# vestee_main.net
KiCad netlist of a schematic drawn in EAGLE
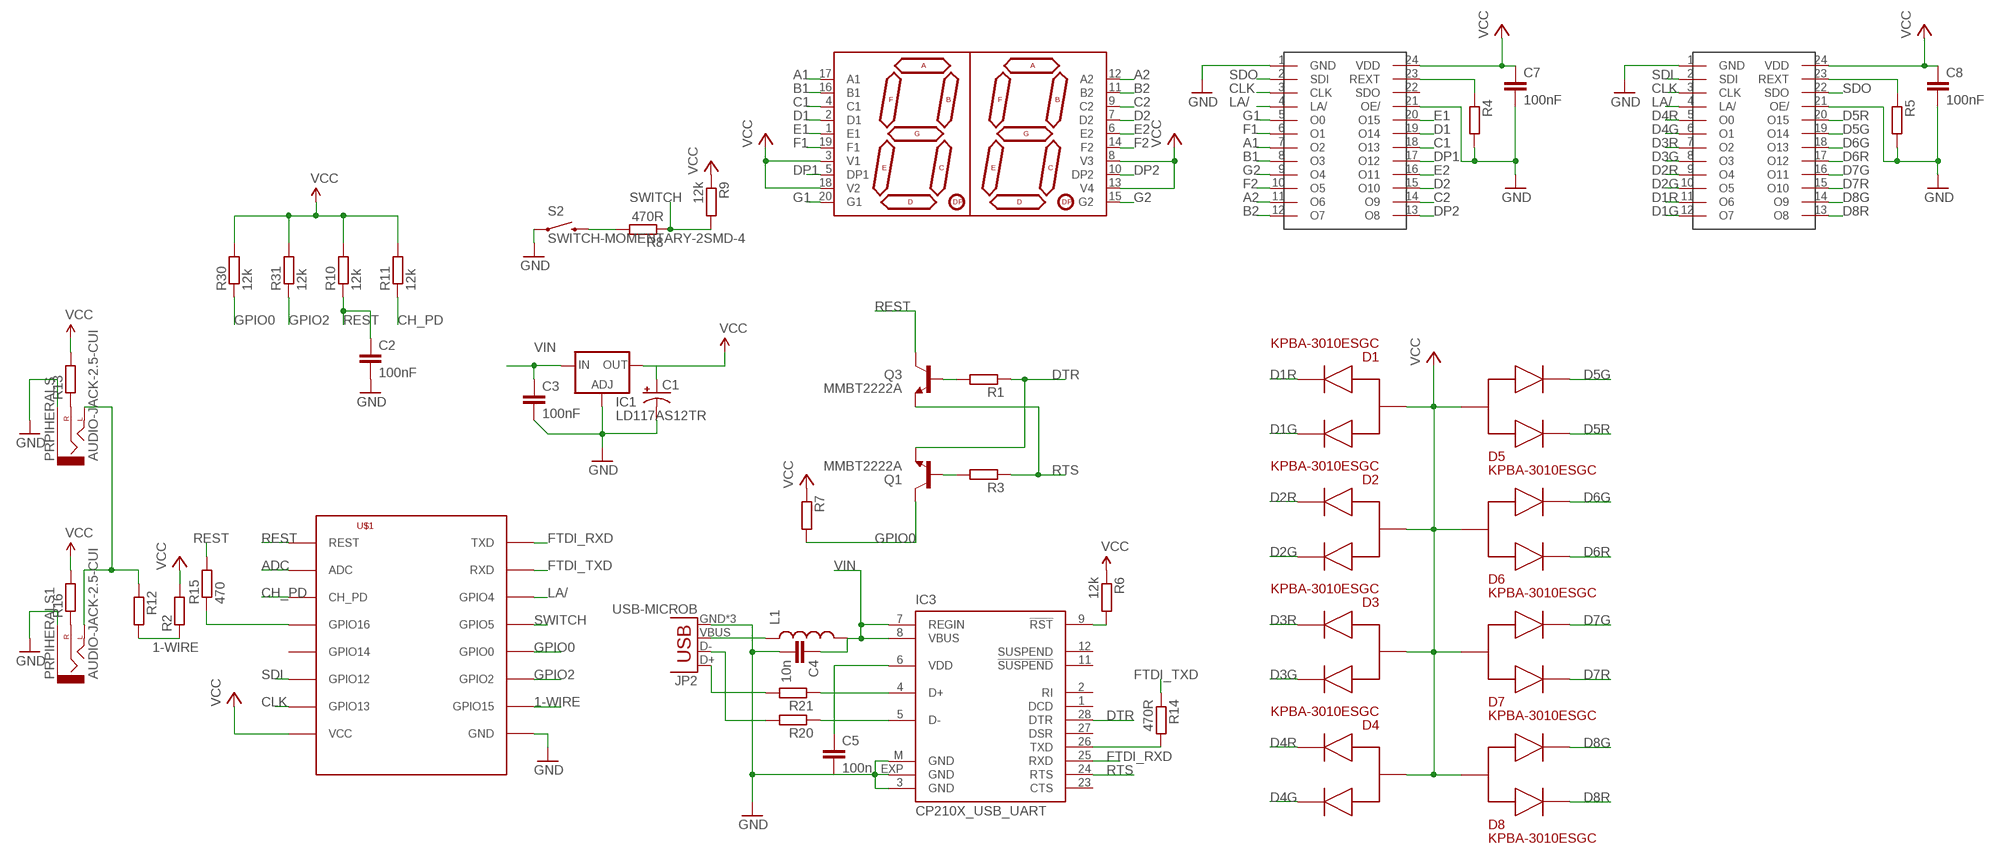
[diagram p0: schematic, sheet 1]

(export (version "E")
  (design (tool "Eeschema 10.0.6"))
  (components
    (comp (ref "C1")
      (value "CAP_POL3528")
      (footprint "eagle-import:EIA3528")
      (libsource (lib "eagle-import") (part "CAP_POL3528"))
    )
    (comp (ref "C2")
      (value "100nF")
      (footprint "eagle-import:C0603")
      (libsource (lib "eagle-import") (part "C-EUC0603"))
    )
    (comp (ref "C3")
      (value "100nF")
      (footprint "eagle-import:C0603")
      (libsource (lib "eagle-import") (part "C-EUC0603"))
    )
    (comp (ref "C4")
      (value "10n")
      (footprint "eagle-import:C0603")
      (libsource (lib "eagle-import") (part "C-EUC0603"))
    )
    (comp (ref "C5")
      (value "100n")
      (footprint "eagle-import:C0603")
      (libsource (lib "eagle-import") (part "C-EUC0603"))
    )
    (comp (ref "C7")
      (value "100nF")
      (footprint "eagle-import:C0603")
      (libsource (lib "eagle-import") (part "C-EUC0603"))
    )
    (comp (ref "C8")
      (value "100nF")
      (footprint "eagle-import:C0603")
      (libsource (lib "eagle-import") (part "C-EUC0603"))
    )
    (comp (ref "D1")
      (value "KPBA-3010ESGC")
      (footprint "eagle-import:APA3010SF4C")
      (libsource (lib "eagle-import") (part "APA3010SF4C"))
    )
    (comp (ref "D2")
      (value "KPBA-3010ESGC")
      (footprint "eagle-import:APA3010SF4C")
      (libsource (lib "eagle-import") (part "APA3010SF4C"))
    )
    (comp (ref "D3")
      (value "KPBA-3010ESGC")
      (footprint "eagle-import:APA3010SF4C")
      (libsource (lib "eagle-import") (part "APA3010SF4C"))
    )
    (comp (ref "D4")
      (value "KPBA-3010ESGC")
      (footprint "eagle-import:APA3010SF4C")
      (libsource (lib "eagle-import") (part "APA3010SF4C"))
    )
    (comp (ref "D5")
      (value "KPBA-3010ESGC")
      (footprint "eagle-import:APA3010SF4C")
      (libsource (lib "eagle-import") (part "APA3010SF4C"))
    )
    (comp (ref "D6")
      (value "KPBA-3010ESGC")
      (footprint "eagle-import:APA3010SF4C")
      (libsource (lib "eagle-import") (part "APA3010SF4C"))
    )
    (comp (ref "D7")
      (value "KPBA-3010ESGC")
      (footprint "eagle-import:APA3010SF4C")
      (libsource (lib "eagle-import") (part "APA3010SF4C"))
    )
    (comp (ref "D8")
      (value "KPBA-3010ESGC")
      (footprint "eagle-import:APA3010SF4C")
      (libsource (lib "eagle-import") (part "APA3010SF4C"))
    )
    (comp (ref "IC1")
      (value "LD117AS12TR")
      (footprint "eagle-import:SOT223")
      (libsource (lib "eagle-import") (part "LD117A?S12TR"))
    )
    (comp (ref "IC3")
      (value "CP210X_USB_UART")
      (footprint "eagle-import:MLP28")
      (libsource (lib "eagle-import") (part "CP210X_USB_UART"))
    )
    (comp (ref "JP2")
      (value "USB-MICROB")
      (footprint "eagle-import:USB-MICROB")
      (libsource (lib "eagle-import") (part "USB-MICROB"))
    )
    (comp (ref "L1")
      (value "INDUCTOR1210")
      (footprint "eagle-import:1210")
      (libsource (lib "eagle-import") (part "INDUCTOR1210"))
    )
    (comp (ref "PRPIHERALS")
      (value "AUDIO-JACK-2.5-CUI")
      (footprint "eagle-import:STEREOJACK2.5_SMD_CUI")
      (libsource (lib "eagle-import") (part "AUDIO-JACK-2.5-CUI"))
    )
    (comp (ref "PRPIHERALS1")
      (value "AUDIO-JACK-2.5-CUI")
      (footprint "eagle-import:STEREOJACK2.5_SMD_CUI")
      (libsource (lib "eagle-import") (part "AUDIO-JACK-2.5-CUI"))
    )
    (comp (ref "Q1")
      (value "MMBT2222A")
      (footprint "eagle-import:SOT23-3")
      (libsource (lib "eagle-import") (part "TRANSISTOR_NPNMMBT2222A"))
    )
    (comp (ref "Q3")
      (value "MMBT2222A")
      (footprint "eagle-import:SOT23-3")
      (libsource (lib "eagle-import") (part "TRANSISTOR_NPNMMBT2222A"))
    )
    (comp (ref "R1")
      (value "R-EU_R0603")
      (footprint "eagle-import:R0603")
      (libsource (lib "eagle-import") (part "R-EU_R0603"))
    )
    (comp (ref "R2")
      (value "R-EU_R0603")
      (footprint "eagle-import:R0603")
      (libsource (lib "eagle-import") (part "R-EU_R0603"))
    )
    (comp (ref "R3")
      (value "R-EU_R0603")
      (footprint "eagle-import:R0603")
      (libsource (lib "eagle-import") (part "R-EU_R0603"))
    )
    (comp (ref "R4")
      (value "R-EU_R0603")
      (footprint "eagle-import:R0603")
      (libsource (lib "eagle-import") (part "R-EU_R0603"))
    )
    (comp (ref "R5")
      (value "R-EU_R0603")
      (footprint "eagle-import:R0603")
      (libsource (lib "eagle-import") (part "R-EU_R0603"))
    )
    (comp (ref "R6")
      (value "12k")
      (footprint "eagle-import:R0603")
      (libsource (lib "eagle-import") (part "R-EU_R0603"))
    )
    (comp (ref "R7")
      (value "R-EU_R0603")
      (footprint "eagle-import:R0603")
      (libsource (lib "eagle-import") (part "R-EU_R0603"))
    )
    (comp (ref "R8")
      (value "470R")
      (footprint "eagle-import:R0603")
      (libsource (lib "eagle-import") (part "R-EU_R0603"))
    )
    (comp (ref "R9")
      (value "12k")
      (footprint "eagle-import:R0603")
      (libsource (lib "eagle-import") (part "R-EU_R0603"))
    )
    (comp (ref "R10")
      (value "12k")
      (footprint "eagle-import:R0603")
      (libsource (lib "eagle-import") (part "R-EU_R0603"))
    )
    (comp (ref "R11")
      (value "12k")
      (footprint "eagle-import:R0603")
      (libsource (lib "eagle-import") (part "R-EU_R0603"))
    )
    (comp (ref "R12")
      (value "R-EU_R0603")
      (footprint "eagle-import:R0603")
      (libsource (lib "eagle-import") (part "R-EU_R0603"))
    )
    (comp (ref "R13")
      (value "R-EU_M1206")
      (footprint "eagle-import:M1206")
      (libsource (lib "eagle-import") (part "R-EU_M1206"))
    )
    (comp (ref "R14")
      (value "470R")
      (footprint "eagle-import:R0603")
      (libsource (lib "eagle-import") (part "R-EU_R0603"))
    )
    (comp (ref "R15")
      (value "470")
      (footprint "eagle-import:R0603")
      (libsource (lib "eagle-import") (part "R-EU_R0603"))
    )
    (comp (ref "R16")
      (value "R-EU_M1206")
      (footprint "eagle-import:M1206")
      (libsource (lib "eagle-import") (part "R-EU_M1206"))
    )
    (comp (ref "R20")
      (value "R-EU_R0603")
      (footprint "eagle-import:R0603")
      (libsource (lib "eagle-import") (part "R-EU_R0603"))
    )
    (comp (ref "R21")
      (value "R-EU_R0603")
      (footprint "eagle-import:R0603")
      (libsource (lib "eagle-import") (part "R-EU_R0603"))
    )
    (comp (ref "R30")
      (value "12k")
      (footprint "eagle-import:R0603")
      (libsource (lib "eagle-import") (part "R-EU_R0603"))
    )
    (comp (ref "R31")
      (value "12k")
      (footprint "eagle-import:R0603")
      (libsource (lib "eagle-import") (part "R-EU_R0603"))
    )
    (comp (ref "S2")
      (value "SWITCH-MOMENTARY-2SMD-4")
      (footprint "eagle-import:TACTILE_SWITCH_TALL")
      (libsource (lib "eagle-import") (part "SWITCH-MOMENTARY-2SMD-4"))
    )
    (comp (ref "U$1")
      (value "ESP8266-07")
      (footprint "eagle-import:ESP-07")
      (libsource (lib "eagle-import") (part "ESP8266-07"))
    )
    (comp (ref "U$2")
      (value "KCDA02-103")
      (footprint "eagle-import:KCDA02-103")
      (libsource (lib "eagle-import") (part "KCDA02-103"))
    )
    (comp (ref "U$3")
      (value "SCT2024CSSG")
      (footprint "eagle-import:SSOP24")
      (libsource (lib "eagle-import") (part "SCT2024CSSG"))
    )
    (comp (ref "U$4")
      (value "SCT2024CSSG")
      (footprint "eagle-import:SSOP24")
      (libsource (lib "eagle-import") (part "SCT2024CSSG"))
    )
  )
  (nets
    (net (code "1") (name "/1-WIRE") (class "Default")
      (node (ref "R12") (pin "2") (pinfunction "2_2") (pintype "passive"))
      (node (ref "R2") (pin "1") (pinfunction "1_1") (pintype "passive"))
      (node (ref "U$1") (pin "GPIO15") (pinfunction "GPIO15_GPIO15") (pintype "input"))
    )
    (net (code "2") (name "/A1") (class "Default")
      (node (ref "U$2") (pin "17") (pinfunction "A1_17") (pintype "bidirectional"))
      (node (ref "U$3") (pin "7") (pinfunction "O2_7") (pintype "bidirectional"))
    )
    (net (code "3") (name "/A2") (class "Default")
      (node (ref "U$2") (pin "12") (pinfunction "A2_12") (pintype "bidirectional"))
      (node (ref "U$3") (pin "11") (pinfunction "O6_11") (pintype "bidirectional"))
    )
    (net (code "4") (name "/ADC") (class "Default")
      (node (ref "U$1") (pin "ADC") (pinfunction "ADC_ADC") (pintype "bidirectional"))
    )
    (net (code "5") (name "/B1") (class "Default")
      (node (ref "U$2") (pin "16") (pinfunction "B1_16") (pintype "bidirectional"))
      (node (ref "U$3") (pin "8") (pinfunction "O3_8") (pintype "bidirectional"))
    )
    (net (code "6") (name "/B2") (class "Default")
      (node (ref "U$2") (pin "11") (pinfunction "B2_11") (pintype "bidirectional"))
      (node (ref "U$3") (pin "12") (pinfunction "O7_12") (pintype "bidirectional"))
    )
    (net (code "7") (name "/C1") (class "Default")
      (node (ref "U$2") (pin "4") (pinfunction "C1_4") (pintype "bidirectional"))
      (node (ref "U$3") (pin "18") (pinfunction "O13_18") (pintype "bidirectional"))
    )
    (net (code "8") (name "/C2") (class "Default")
      (node (ref "U$2") (pin "9") (pinfunction "C2_9") (pintype "bidirectional"))
      (node (ref "U$3") (pin "14") (pinfunction "O9_14") (pintype "bidirectional"))
    )
    (net (code "9") (name "/CH_PD") (class "Default")
      (node (ref "R11") (pin "1") (pinfunction "1_1") (pintype "passive"))
      (node (ref "U$1") (pin "CH_PD") (pinfunction "CH_PD_CH_PD") (pintype "input"))
    )
    (net (code "10") (name "/CLK") (class "Default")
      (node (ref "U$1") (pin "GPIO13") (pinfunction "GPIO13_GPIO13") (pintype "bidirectional"))
      (node (ref "U$3") (pin "3") (pinfunction "CLK_3") (pintype "bidirectional"))
      (node (ref "U$4") (pin "3") (pinfunction "CLK_3") (pintype "bidirectional"))
    )
    (net (code "11") (name "/D1") (class "Default")
      (node (ref "U$2") (pin "2") (pinfunction "D1_2") (pintype "bidirectional"))
      (node (ref "U$3") (pin "19") (pinfunction "O14_19") (pintype "bidirectional"))
    )
    (net (code "12") (name "/D1G") (class "Default")
      (node (ref "D1") (pin "3") (pinfunction "3_3") (pintype "bidirectional"))
      (node (ref "U$4") (pin "12") (pinfunction "O7_12") (pintype "bidirectional"))
    )
    (net (code "13") (name "/D1R") (class "Default")
      (node (ref "D1") (pin "2") (pinfunction "2_2") (pintype "bidirectional"))
      (node (ref "U$4") (pin "11") (pinfunction "O6_11") (pintype "bidirectional"))
    )
    (net (code "14") (name "/D2") (class "Default")
      (node (ref "U$2") (pin "7") (pinfunction "D2_7") (pintype "bidirectional"))
      (node (ref "U$3") (pin "15") (pinfunction "O10_15") (pintype "bidirectional"))
    )
    (net (code "15") (name "/D2G") (class "Default")
      (node (ref "D2") (pin "3") (pinfunction "3_3") (pintype "bidirectional"))
      (node (ref "U$4") (pin "10") (pinfunction "O5_10") (pintype "bidirectional"))
    )
    (net (code "16") (name "/D2R") (class "Default")
      (node (ref "D2") (pin "2") (pinfunction "2_2") (pintype "bidirectional"))
      (node (ref "U$4") (pin "9") (pinfunction "O4_9") (pintype "bidirectional"))
    )
    (net (code "17") (name "/D3G") (class "Default")
      (node (ref "D3") (pin "3") (pinfunction "3_3") (pintype "bidirectional"))
      (node (ref "U$4") (pin "8") (pinfunction "O3_8") (pintype "bidirectional"))
    )
    (net (code "18") (name "/D3R") (class "Default")
      (node (ref "D3") (pin "2") (pinfunction "2_2") (pintype "bidirectional"))
      (node (ref "U$4") (pin "7") (pinfunction "O2_7") (pintype "bidirectional"))
    )
    (net (code "19") (name "/D4G") (class "Default")
      (node (ref "D4") (pin "3") (pinfunction "3_3") (pintype "bidirectional"))
      (node (ref "U$4") (pin "6") (pinfunction "O1_6") (pintype "bidirectional"))
    )
    (net (code "20") (name "/D4R") (class "Default")
      (node (ref "D4") (pin "2") (pinfunction "2_2") (pintype "bidirectional"))
      (node (ref "U$4") (pin "5") (pinfunction "O0_5") (pintype "bidirectional"))
    )
    (net (code "21") (name "/D5G") (class "Default")
      (node (ref "D5") (pin "3") (pinfunction "3_3") (pintype "bidirectional"))
      (node (ref "U$4") (pin "19") (pinfunction "O14_19") (pintype "bidirectional"))
    )
    (net (code "22") (name "/D5R") (class "Default")
      (node (ref "D5") (pin "2") (pinfunction "2_2") (pintype "bidirectional"))
      (node (ref "U$4") (pin "20") (pinfunction "O15_20") (pintype "bidirectional"))
    )
    (net (code "23") (name "/D6G") (class "Default")
      (node (ref "D6") (pin "3") (pinfunction "3_3") (pintype "bidirectional"))
      (node (ref "U$4") (pin "18") (pinfunction "O13_18") (pintype "bidirectional"))
    )
    (net (code "24") (name "/D6R") (class "Default")
      (node (ref "D6") (pin "2") (pinfunction "2_2") (pintype "bidirectional"))
      (node (ref "U$4") (pin "17") (pinfunction "O12_17") (pintype "bidirectional"))
    )
    (net (code "25") (name "/D7G") (class "Default")
      (node (ref "D7") (pin "3") (pinfunction "3_3") (pintype "bidirectional"))
      (node (ref "U$4") (pin "16") (pinfunction "O11_16") (pintype "bidirectional"))
    )
    (net (code "26") (name "/D7R") (class "Default")
      (node (ref "D7") (pin "2") (pinfunction "2_2") (pintype "bidirectional"))
      (node (ref "U$4") (pin "15") (pinfunction "O10_15") (pintype "bidirectional"))
    )
    (net (code "27") (name "/D8G") (class "Default")
      (node (ref "D8") (pin "3") (pinfunction "3_3") (pintype "bidirectional"))
      (node (ref "U$4") (pin "14") (pinfunction "O9_14") (pintype "bidirectional"))
    )
    (net (code "28") (name "/D8R") (class "Default")
      (node (ref "D8") (pin "2") (pinfunction "2_2") (pintype "bidirectional"))
      (node (ref "U$4") (pin "13") (pinfunction "O8_13") (pintype "bidirectional"))
    )
    (net (code "29") (name "/DP1") (class "Default")
      (node (ref "U$2") (pin "5") (pinfunction "DP1_5") (pintype "bidirectional"))
      (node (ref "U$3") (pin "17") (pinfunction "O12_17") (pintype "bidirectional"))
    )
    (net (code "30") (name "/DP2") (class "Default")
      (node (ref "U$2") (pin "10") (pinfunction "DP2_10") (pintype "bidirectional"))
      (node (ref "U$3") (pin "13") (pinfunction "O8_13") (pintype "bidirectional"))
    )
    (net (code "31") (name "/DTR") (class "Default")
      (node (ref "IC3") (pin "28") (pinfunction "DTR_28") (pintype "output"))
      (node (ref "Q1") (pin "2") (pinfunction "E_2") (pintype "passive"))
      (node (ref "R1") (pin "1") (pinfunction "1_1") (pintype "passive"))
    )
    (net (code "32") (name "/E1") (class "Default")
      (node (ref "U$2") (pin "1") (pinfunction "E1_1") (pintype "bidirectional"))
      (node (ref "U$3") (pin "20") (pinfunction "O15_20") (pintype "bidirectional"))
    )
    (net (code "33") (name "/E2") (class "Default")
      (node (ref "U$2") (pin "6") (pinfunction "E2_6") (pintype "bidirectional"))
      (node (ref "U$3") (pin "16") (pinfunction "O11_16") (pintype "bidirectional"))
    )
    (net (code "34") (name "/F1") (class "Default")
      (node (ref "U$2") (pin "19") (pinfunction "F1_19") (pintype "bidirectional"))
      (node (ref "U$3") (pin "6") (pinfunction "O1_6") (pintype "bidirectional"))
    )
    (net (code "35") (name "/F2") (class "Default")
      (node (ref "U$2") (pin "14") (pinfunction "F2_14") (pintype "bidirectional"))
      (node (ref "U$3") (pin "10") (pinfunction "O5_10") (pintype "bidirectional"))
    )
    (net (code "36") (name "/FTDI_RXD") (class "Default")
      (node (ref "IC3") (pin "25") (pinfunction "RXD_25") (pintype "input"))
      (node (ref "U$1") (pin "TXD") (pinfunction "TXD_TXD") (pintype "output"))
    )
    (net (code "37") (name "/FTDI_TXD") (class "Default")
      (node (ref "R14") (pin "1") (pinfunction "1_1") (pintype "passive"))
      (node (ref "U$1") (pin "RXD") (pinfunction "RXD_RXD") (pintype "input"))
    )
    (net (code "38") (name "/G1") (class "Default")
      (node (ref "U$2") (pin "20") (pinfunction "G1_20") (pintype "bidirectional"))
      (node (ref "U$3") (pin "5") (pinfunction "O0_5") (pintype "bidirectional"))
    )
    (net (code "39") (name "/G2") (class "Default")
      (node (ref "U$2") (pin "15") (pinfunction "G2_15") (pintype "bidirectional"))
      (node (ref "U$3") (pin "9") (pinfunction "O4_9") (pintype "bidirectional"))
    )
    (net (code "40") (name "/GPIO0") (class "Default")
      (node (ref "Q1") (pin "3") (pinfunction "C_3") (pintype "passive"))
      (node (ref "R30") (pin "1") (pinfunction "1_1") (pintype "passive"))
      (node (ref "R7") (pin "2") (pinfunction "2_2") (pintype "passive"))
      (node (ref "U$1") (pin "GPIO0") (pinfunction "GPIO0_GPIO0") (pintype "bidirectional"))
    )
    (net (code "41") (name "/GPIO2") (class "Default")
      (node (ref "R31") (pin "1") (pinfunction "1_1") (pintype "passive"))
      (node (ref "U$1") (pin "GPIO2") (pinfunction "GPIO2_GPIO2") (pintype "bidirectional"))
    )
    (net (code "42") (name "/LA{slash}") (class "Default")
      (node (ref "U$1") (pin "GPIO4") (pinfunction "GPIO4_GPIO4") (pintype "bidirectional"))
      (node (ref "U$3") (pin "4") (pinfunction "LA/_4") (pintype "bidirectional"))
      (node (ref "U$4") (pin "4") (pinfunction "LA/_4") (pintype "bidirectional"))
    )
    (net (code "43") (name "/REST") (class "Default")
      (node (ref "C2") (pin "1") (pinfunction "1_1") (pintype "passive"))
      (node (ref "Q3") (pin "3") (pinfunction "C_3") (pintype "passive"))
      (node (ref "R10") (pin "1") (pinfunction "1_1") (pintype "passive"))
      (node (ref "R15") (pin "2") (pinfunction "2_2") (pintype "passive"))
      (node (ref "U$1") (pin "REST") (pinfunction "REST_REST") (pintype "bidirectional"))
    )
    (net (code "44") (name "/RTS") (class "Default")
      (node (ref "IC3") (pin "24") (pinfunction "RTS_24") (pintype "output"))
      (node (ref "Q3") (pin "2") (pinfunction "E_2") (pintype "passive"))
      (node (ref "R3") (pin "1") (pinfunction "1_1") (pintype "passive"))
    )
    (net (code "45") (name "/SDI") (class "Default")
      (node (ref "U$1") (pin "GPIO12") (pinfunction "GPIO12_GPIO12") (pintype "bidirectional"))
      (node (ref "U$4") (pin "2") (pinfunction "SDI_2") (pintype "bidirectional"))
    )
    (net (code "46") (name "/SDO") (class "Default")
      (node (ref "U$3") (pin "2") (pinfunction "SDI_2") (pintype "bidirectional"))
      (node (ref "U$4") (pin "22") (pinfunction "SDO_22") (pintype "bidirectional"))
    )
    (net (code "47") (name "/SWITCH") (class "Default")
      (node (ref "R8") (pin "1") (pinfunction "1_1") (pintype "passive"))
      (node (ref "R9") (pin "2") (pinfunction "2_2") (pintype "passive"))
      (node (ref "U$1") (pin "GPIO5") (pinfunction "GPIO5_GPIO5") (pintype "bidirectional"))
    )
    (net (code "48") (name "/VIN") (class "Default")
      (node (ref "C3") (pin "1") (pinfunction "1_1") (pintype "passive"))
      (node (ref "C4") (pin "1") (pinfunction "1_1") (pintype "passive"))
      (node (ref "IC1") (pin "3") (pinfunction "IN_3") (pintype "input"))
      (node (ref "IC3") (pin "7") (pinfunction "REGIN_7") (pintype "passive"))
      (node (ref "IC3") (pin "8") (pinfunction "VBUS_8") (pintype "input"))
      (node (ref "L1") (pin "2") (pinfunction "2_2") (pintype "passive"))
    )
    (net (code "49") (name "GND") (class "Default")
      (node (ref "C1") (pin "C") (pinfunction "-_C") (pintype "passive"))
      (node (ref "C2") (pin "2") (pinfunction "2_2") (pintype "passive"))
      (node (ref "C3") (pin "2") (pinfunction "2_2") (pintype "passive"))
      (node (ref "C4") (pin "2") (pinfunction "2_2") (pintype "passive"))
      (node (ref "C5") (pin "2") (pinfunction "2_2") (pintype "passive"))
      (node (ref "C7") (pin "2") (pinfunction "2_2") (pintype "passive"))
      (node (ref "C8") (pin "2") (pinfunction "2_2") (pintype "passive"))
      (node (ref "IC1") (pin "1") (pinfunction "ADJ_1") (pintype "input"))
      (node (ref "IC3") (pin "3") (pinfunction "GND_3") (pintype "power_in"))
      (node (ref "IC3") (pin "EXP") (pinfunction "GND_EXP") (pintype "power_in"))
      (node (ref "IC3") (pin "M") (pinfunction "GND_M") (pintype "power_in"))
      (node (ref "JP2") (pin "GND") (pinfunction "GND_GND") (pintype "bidirectional"))
      (node (ref "JP2") (pin "MT1") (pinfunction "GND_MT1") (pintype "bidirectional"))
      (node (ref "JP2") (pin "MT2") (pinfunction "GND_MT2") (pintype "bidirectional"))
      (node (ref "PRPIHERALS") (pin "1") (pinfunction "SLEEVE_1") (pintype "bidirectional"))
      (node (ref "PRPIHERALS1") (pin "1") (pinfunction "SLEEVE_1") (pintype "bidirectional"))
      (node (ref "R4") (pin "2") (pinfunction "2_2") (pintype "passive"))
      (node (ref "R5") (pin "2") (pinfunction "2_2") (pintype "passive"))
      (node (ref "S2") (pin "A2") (pinfunction "1_A2") (pintype "passive"))
      (node (ref "U$1") (pin "GND") (pinfunction "GND_GND") (pintype "power_in"))
      (node (ref "U$3") (pin "1") (pinfunction "GND_1") (pintype "bidirectional"))
      (node (ref "U$3") (pin "21") (pinfunction "OE/_21") (pintype "bidirectional"))
      (node (ref "U$4") (pin "1") (pinfunction "GND_1") (pintype "bidirectional"))
      (node (ref "U$4") (pin "21") (pinfunction "OE/_21") (pintype "bidirectional"))
    )
    (net (code "50") (name "Net-(IC3-D+)") (class "Default")
      (node (ref "IC3") (pin "4") (pinfunction "D+_4") (pintype "bidirectional"))
      (node (ref "R21") (pin "1") (pinfunction "1_1") (pintype "passive"))
    )
    (net (code "51") (name "Net-(IC3-D-)") (class "Default")
      (node (ref "IC3") (pin "5") (pinfunction "D-_5") (pintype "bidirectional"))
      (node (ref "R20") (pin "1") (pinfunction "1_1") (pintype "passive"))
    )
    (net (code "52") (name "Net-(IC3-TXD)") (class "Default")
      (node (ref "IC3") (pin "26") (pinfunction "TXD_26") (pintype "output"))
      (node (ref "R14") (pin "2") (pinfunction "2_2") (pintype "passive"))
    )
    (net (code "53") (name "Net-(IC3-VDD)") (class "Default")
      (node (ref "C5") (pin "1") (pinfunction "1_1") (pintype "passive"))
      (node (ref "IC3") (pin "6") (pinfunction "VDD_6") (pintype "power_in"))
    )
    (net (code "54") (name "Net-(IC3-~{RST})") (class "Default")
      (node (ref "IC3") (pin "9") (pinfunction "~{RST}_9") (pintype "bidirectional"))
      (node (ref "R6") (pin "2") (pinfunction "2_2") (pintype "passive"))
    )
    (net (code "55") (name "Net-(JP2-PadD+)") (class "Default")
      (node (ref "JP2") (pin "D+") (pinfunction "D+_D+") (pintype "bidirectional"))
      (node (ref "R21") (pin "2") (pinfunction "2_2") (pintype "passive"))
    )
    (net (code "56") (name "Net-(JP2-PadD-)") (class "Default")
      (node (ref "JP2") (pin "D-") (pinfunction "D-_D-") (pintype "bidirectional"))
      (node (ref "R20") (pin "2") (pinfunction "2_2") (pintype "passive"))
    )
    (net (code "57") (name "Net-(JP2-PadVBUS)") (class "Default")
      (node (ref "JP2") (pin "VBUS") (pinfunction "VBUS_VBUS") (pintype "bidirectional"))
      (node (ref "L1") (pin "1") (pinfunction "1_1") (pintype "passive"))
    )
    (net (code "58") (name "Net-(PRPIHERALS-LEFT)") (class "Default")
      (node (ref "PRPIHERALS") (pin "3") (pinfunction "LEFT_3") (pintype "bidirectional"))
      (node (ref "PRPIHERALS1") (pin "3") (pinfunction "LEFT_3") (pintype "bidirectional"))
      (node (ref "R12") (pin "1") (pinfunction "1_1") (pintype "passive"))
    )
    (net (code "59") (name "Net-(PRPIHERALS-RIGHT)") (class "Default")
      (node (ref "PRPIHERALS") (pin "2") (pinfunction "RIGHT_2") (pintype "bidirectional"))
      (node (ref "R13") (pin "1") (pinfunction "1_1") (pintype "passive"))
    )
    (net (code "60") (name "Net-(PRPIHERALS1-RIGHT)") (class "Default")
      (node (ref "PRPIHERALS1") (pin "2") (pinfunction "RIGHT_2") (pintype "bidirectional"))
      (node (ref "R16") (pin "1") (pinfunction "1_1") (pintype "passive"))
    )
    (net (code "61") (name "Net-(Q1-B)") (class "Default")
      (node (ref "Q1") (pin "1") (pinfunction "B_1") (pintype "passive"))
      (node (ref "R3") (pin "2") (pinfunction "2_2") (pintype "passive"))
    )
    (net (code "62") (name "Net-(Q3-B)") (class "Default")
      (node (ref "Q3") (pin "1") (pinfunction "B_1") (pintype "passive"))
      (node (ref "R1") (pin "2") (pinfunction "2_2") (pintype "passive"))
    )
    (net (code "63") (name "Net-(R15-Pad1)") (class "Default")
      (node (ref "R15") (pin "1") (pinfunction "1_1") (pintype "passive"))
      (node (ref "U$1") (pin "GPIO16") (pinfunction "GPIO16_GPIO16") (pintype "bidirectional"))
    )
    (net (code "64") (name "Net-(S2-2)") (class "Default")
      (node (ref "R8") (pin "2") (pinfunction "2_2") (pintype "passive"))
      (node (ref "S2") (pin "B2") (pinfunction "2_B2") (pintype "passive"))
    )
    (net (code "65") (name "Net-(U$3-REXT)") (class "Default")
      (node (ref "R4") (pin "1") (pinfunction "1_1") (pintype "passive"))
      (node (ref "U$3") (pin "23") (pinfunction "REXT_23") (pintype "bidirectional"))
    )
    (net (code "66") (name "Net-(U$4-REXT)") (class "Default")
      (node (ref "R5") (pin "1") (pinfunction "1_1") (pintype "passive"))
      (node (ref "U$4") (pin "23") (pinfunction "REXT_23") (pintype "bidirectional"))
    )
    (net (code "67") (name "VCC") (class "Default")
      (node (ref "C1") (pin "A") (pinfunction "+_A") (pintype "passive"))
      (node (ref "C7") (pin "1") (pinfunction "1_1") (pintype "passive"))
      (node (ref "C8") (pin "1") (pinfunction "1_1") (pintype "passive"))
      (node (ref "D1") (pin "COM") (pinfunction "COM_COM") (pintype "bidirectional"))
      (node (ref "D2") (pin "COM") (pinfunction "COM_COM") (pintype "bidirectional"))
      (node (ref "D3") (pin "COM") (pinfunction "COM_COM") (pintype "bidirectional"))
      (node (ref "D4") (pin "COM") (pinfunction "COM_COM") (pintype "bidirectional"))
      (node (ref "D5") (pin "COM") (pinfunction "COM_COM") (pintype "bidirectional"))
      (node (ref "D6") (pin "COM") (pinfunction "COM_COM") (pintype "bidirectional"))
      (node (ref "D7") (pin "COM") (pinfunction "COM_COM") (pintype "bidirectional"))
      (node (ref "D8") (pin "COM") (pinfunction "COM_COM") (pintype "bidirectional"))
      (node (ref "IC1") (pin "4") (pinfunction "OUT_4") (pintype "passive"))
      (node (ref "R10") (pin "2") (pinfunction "2_2") (pintype "passive"))
      (node (ref "R11") (pin "2") (pinfunction "2_2") (pintype "passive"))
      (node (ref "R13") (pin "2") (pinfunction "2_2") (pintype "passive"))
      (node (ref "R16") (pin "2") (pinfunction "2_2") (pintype "passive"))
      (node (ref "R2") (pin "2") (pinfunction "2_2") (pintype "passive"))
      (node (ref "R30") (pin "2") (pinfunction "2_2") (pintype "passive"))
      (node (ref "R31") (pin "2") (pinfunction "2_2") (pintype "passive"))
      (node (ref "R6") (pin "1") (pinfunction "1_1") (pintype "passive"))
      (node (ref "R7") (pin "1") (pinfunction "1_1") (pintype "passive"))
      (node (ref "R9") (pin "1") (pinfunction "1_1") (pintype "passive"))
      (node (ref "U$1") (pin "VCC") (pinfunction "VCC_VCC") (pintype "power_in"))
      (node (ref "U$2") (pin "13") (pinfunction "V4_13") (pintype "bidirectional"))
      (node (ref "U$2") (pin "18") (pinfunction "V2_18") (pintype "bidirectional"))
      (node (ref "U$2") (pin "3") (pinfunction "V1_3") (pintype "bidirectional"))
      (node (ref "U$2") (pin "8") (pinfunction "V3_8") (pintype "bidirectional"))
      (node (ref "U$3") (pin "24") (pinfunction "VDD_24") (pintype "bidirectional"))
      (node (ref "U$4") (pin "24") (pinfunction "VDD_24") (pintype "bidirectional"))
    )
    (net (code "68") (name "unconnected-(IC3-CTS-Pad23)") (class "Default")
      (node (ref "IC3") (pin "23") (pinfunction "CTS_23") (pintype "input"))
    )
    (net (code "69") (name "unconnected-(IC3-DCD-Pad1)") (class "Default")
      (node (ref "IC3") (pin "1") (pinfunction "DCD_1") (pintype "input"))
    )
    (net (code "70") (name "unconnected-(IC3-DSR-Pad27)") (class "Default")
      (node (ref "IC3") (pin "27") (pinfunction "DSR_27") (pintype "input"))
    )
    (net (code "71") (name "unconnected-(IC3-RI-Pad2)") (class "Default")
      (node (ref "IC3") (pin "2") (pinfunction "RI_2") (pintype "input"))
    )
    (net (code "72") (name "unconnected-(IC3-SUSPEND-Pad12)") (class "Default")
      (node (ref "IC3") (pin "12") (pinfunction "SUSPEND_12") (pintype "output"))
    )
    (net (code "73") (name "unconnected-(IC3-~{SUSPEND}-Pad11)") (class "Default")
      (node (ref "IC3") (pin "11") (pinfunction "~{SUSPEND}_11") (pintype "output"))
    )
    (net (code "74") (name "unconnected-(U$1-PadGPIO14)") (class "Default")
      (node (ref "U$1") (pin "GPIO14") (pinfunction "GPIO14_GPIO14") (pintype "bidirectional"))
    )
    (net (code "75") (name "unconnected-(U$3-SDO-Pad22)") (class "Default")
      (node (ref "U$3") (pin "22") (pinfunction "SDO_22") (pintype "bidirectional"))
    )
  )
)
